# reciever.net
KiCad netlist of a schematic drawn in EAGLE
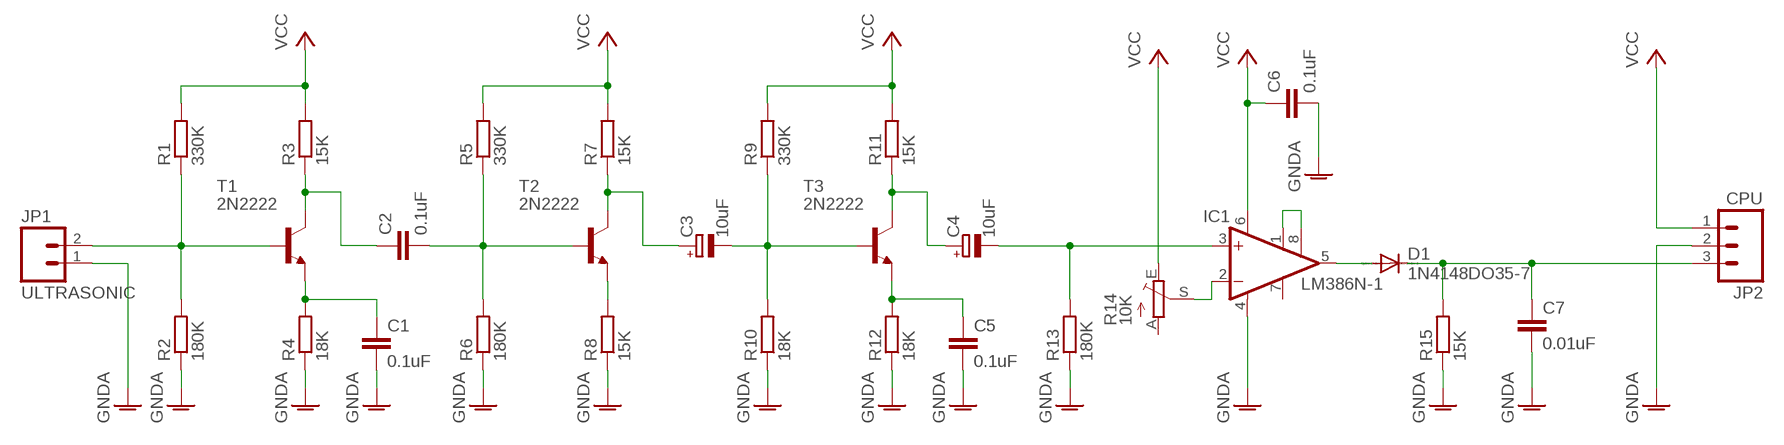
[diagram p0: schematic, sheet 1]

(export (version "E")
  (design (tool "Eeschema 10.0.6"))
  (components
    (comp (ref "C1")
      (value "0.1uF")
      (footprint "eagle-import:C050-025X075")
      (libsource (lib "eagle-import") (part "C-EU050-025X075"))
    )
    (comp (ref "C2")
      (value "0.1uF")
      (footprint "eagle-import:C050-025X075")
      (libsource (lib "eagle-import") (part "C-EU050-025X075"))
    )
    (comp (ref "C3")
      (value "10uF")
      (footprint "eagle-import:E2,5-5")
      (libsource (lib "eagle-import") (part "CPOL-EUE2.5-5"))
    )
    (comp (ref "C4")
      (value "10uF")
      (footprint "eagle-import:E2,5-5")
      (libsource (lib "eagle-import") (part "CPOL-EUE2.5-5"))
    )
    (comp (ref "C5")
      (value "0.1uF")
      (footprint "eagle-import:C050-025X075")
      (libsource (lib "eagle-import") (part "C-EU050-025X075"))
    )
    (comp (ref "C6")
      (value "0.1uF")
      (footprint "eagle-import:C050-025X075")
      (libsource (lib "eagle-import") (part "C-EU050-025X075"))
    )
    (comp (ref "C7")
      (value "0.01uF")
      (footprint "eagle-import:C050-025X075")
      (libsource (lib "eagle-import") (part "C-EU050-025X075"))
    )
    (comp (ref "D1")
      (value "1N4148DO35-7")
      (footprint "eagle-import:DO35-7")
      (libsource (lib "eagle-import") (part "1N4148DO35-7"))
    )
    (comp (ref "IC1")
      (value "LM386N-1")
      (footprint "eagle-import:DIL08")
      (libsource (lib "eagle-import") (part "LM386?-N1"))
    )
    (comp (ref "JP1")
      (value "ULTRASONIC")
      (footprint "eagle-import:JST-2-PTH-VERT")
      (libsource (lib "eagle-import") (part "M02JST-PTH-VERT"))
    )
    (comp (ref "JP2")
      (value "CPU")
      (footprint "eagle-import:JST-3-PTH-VERT")
      (libsource (lib "eagle-import") (part "M03JST-PTH-VERT"))
    )
    (comp (ref "R1")
      (value "330K")
      (footprint "eagle-import:0204_7")
      (libsource (lib "eagle-import") (part "R-EU_0204/7"))
    )
    (comp (ref "R2")
      (value "180K")
      (footprint "eagle-import:0204_7")
      (libsource (lib "eagle-import") (part "R-EU_0204/7"))
    )
    (comp (ref "R3")
      (value "15K")
      (footprint "eagle-import:0204_7")
      (libsource (lib "eagle-import") (part "R-EU_0204/7"))
    )
    (comp (ref "R4")
      (value "18K")
      (footprint "eagle-import:0204_7")
      (libsource (lib "eagle-import") (part "R-EU_0204/7"))
    )
    (comp (ref "R5")
      (value "330K")
      (footprint "eagle-import:0204_7")
      (libsource (lib "eagle-import") (part "R-EU_0204/7"))
    )
    (comp (ref "R6")
      (value "180K")
      (footprint "eagle-import:0204_7")
      (libsource (lib "eagle-import") (part "R-EU_0204/7"))
    )
    (comp (ref "R7")
      (value "15K")
      (footprint "eagle-import:0204_7")
      (libsource (lib "eagle-import") (part "R-EU_0204/7"))
    )
    (comp (ref "R8")
      (value "15K")
      (footprint "eagle-import:0204_7")
      (libsource (lib "eagle-import") (part "R-EU_0204/7"))
    )
    (comp (ref "R9")
      (value "330K")
      (footprint "eagle-import:0204_7")
      (libsource (lib "eagle-import") (part "R-EU_0204/7"))
    )
    (comp (ref "R10")
      (value "18K")
      (footprint "eagle-import:0204_7")
      (libsource (lib "eagle-import") (part "R-EU_0204/7"))
    )
    (comp (ref "R11")
      (value "15K")
      (footprint "eagle-import:0204_7")
      (libsource (lib "eagle-import") (part "R-EU_0204/7"))
    )
    (comp (ref "R12")
      (value "18K")
      (footprint "eagle-import:0204_7")
      (libsource (lib "eagle-import") (part "R-EU_0204/7"))
    )
    (comp (ref "R13")
      (value "180K")
      (footprint "eagle-import:0204_7")
      (libsource (lib "eagle-import") (part "R-EU_0204/7"))
    )
    (comp (ref "R14")
      (value "10K")
      (footprint "eagle-import:B25P")
      (libsource (lib "eagle-import") (part "TRIM_EU-B25P"))
    )
    (comp (ref "R15")
      (value "15K")
      (footprint "eagle-import:0204_7")
      (libsource (lib "eagle-import") (part "R-EU_0204/7"))
    )
    (comp (ref "T1")
      (value "2N2222")
      (footprint "eagle-import:TO92-EBC")
      (libsource (lib "eagle-import") (part "-NPN-TO92-EBC"))
    )
    (comp (ref "T2")
      (value "2N2222")
      (footprint "eagle-import:TO92-EBC")
      (libsource (lib "eagle-import") (part "-NPN-TO92-EBC"))
    )
    (comp (ref "T3")
      (value "2N2222")
      (footprint "eagle-import:TO92-EBC")
      (libsource (lib "eagle-import") (part "-NPN-TO92-EBC"))
    )
  )
  (nets
    (net (code "1") (name "GNDA") (class "Default")
      (node (ref "C1") (pin "2") (pinfunction "2_2") (pintype "passive"))
      (node (ref "C5") (pin "2") (pinfunction "2_2") (pintype "passive"))
      (node (ref "C6") (pin "2") (pinfunction "2_2") (pintype "passive"))
      (node (ref "C7") (pin "2") (pinfunction "2_2") (pintype "passive"))
      (node (ref "IC1") (pin "4") (pinfunction "GND_4") (pintype "power_in"))
      (node (ref "JP1") (pin "1") (pinfunction "1_1") (pintype "passive"))
      (node (ref "JP2") (pin "2") (pinfunction "2_2") (pintype "passive"))
      (node (ref "R10") (pin "1") (pinfunction "1_1") (pintype "passive"))
      (node (ref "R12") (pin "1") (pinfunction "1_1") (pintype "passive"))
      (node (ref "R13") (pin "1") (pinfunction "1_1") (pintype "passive"))
      (node (ref "R15") (pin "1") (pinfunction "1_1") (pintype "passive"))
      (node (ref "R2") (pin "1") (pinfunction "1_1") (pintype "passive"))
      (node (ref "R4") (pin "1") (pinfunction "1_1") (pintype "passive"))
      (node (ref "R6") (pin "1") (pinfunction "1_1") (pintype "passive"))
      (node (ref "R8") (pin "1") (pinfunction "1_1") (pintype "passive"))
    )
    (net (code "2") (name "Net-(C1-Pad1)") (class "Default")
      (node (ref "C1") (pin "1") (pinfunction "1_1") (pintype "passive"))
      (node (ref "R4") (pin "2") (pinfunction "2_2") (pintype "passive"))
      (node (ref "T1") (pin "E") (pinfunction "E_E") (pintype "passive"))
    )
    (net (code "3") (name "Net-(C2-Pad1)") (class "Default")
      (node (ref "C2") (pin "1") (pinfunction "1_1") (pintype "passive"))
      (node (ref "R3") (pin "1") (pinfunction "1_1") (pintype "passive"))
      (node (ref "T1") (pin "C") (pinfunction "C_C") (pintype "passive"))
    )
    (net (code "4") (name "Net-(C2-Pad2)") (class "Default")
      (node (ref "C2") (pin "2") (pinfunction "2_2") (pintype "passive"))
      (node (ref "R5") (pin "1") (pinfunction "1_1") (pintype "passive"))
      (node (ref "R6") (pin "2") (pinfunction "2_2") (pintype "passive"))
      (node (ref "T2") (pin "B") (pinfunction "B_B") (pintype "passive"))
    )
    (net (code "5") (name "Net-(C3-Pad+)") (class "Default")
      (node (ref "C3") (pin "+") (pinfunction "+_+") (pintype "passive"))
      (node (ref "R7") (pin "1") (pinfunction "1_1") (pintype "passive"))
      (node (ref "T2") (pin "C") (pinfunction "C_C") (pintype "passive"))
    )
    (net (code "6") (name "Net-(C3-Pad-)") (class "Default")
      (node (ref "C3") (pin "-") (pinfunction "-_-") (pintype "passive"))
      (node (ref "R10") (pin "2") (pinfunction "2_2") (pintype "passive"))
      (node (ref "R9") (pin "1") (pinfunction "1_1") (pintype "passive"))
      (node (ref "T3") (pin "B") (pinfunction "B_B") (pintype "passive"))
    )
    (net (code "7") (name "Net-(C4-Pad+)") (class "Default")
      (node (ref "C4") (pin "+") (pinfunction "+_+") (pintype "passive"))
      (node (ref "R11") (pin "1") (pinfunction "1_1") (pintype "passive"))
      (node (ref "T3") (pin "C") (pinfunction "C_C") (pintype "passive"))
    )
    (net (code "8") (name "Net-(C5-Pad1)") (class "Default")
      (node (ref "C5") (pin "1") (pinfunction "1_1") (pintype "passive"))
      (node (ref "R12") (pin "2") (pinfunction "2_2") (pintype "passive"))
      (node (ref "T3") (pin "E") (pinfunction "E_E") (pintype "passive"))
    )
    (net (code "9") (name "Net-(C7-Pad1)") (class "Default")
      (node (ref "C7") (pin "1") (pinfunction "1_1") (pintype "passive"))
      (node (ref "D1") (pin "C") (pinfunction "C_C") (pintype "passive"))
      (node (ref "JP2") (pin "3") (pinfunction "3_3") (pintype "passive"))
      (node (ref "R15") (pin "2") (pinfunction "2_2") (pintype "passive"))
    )
    (net (code "10") (name "Net-(IC1-+IN)") (class "Default")
      (node (ref "C4") (pin "-") (pinfunction "-_-") (pintype "passive"))
      (node (ref "IC1") (pin "3") (pinfunction "+IN_3") (pintype "input"))
      (node (ref "R13") (pin "2") (pinfunction "2_2") (pintype "passive"))
    )
    (net (code "11") (name "Net-(IC1--IN)") (class "Default")
      (node (ref "IC1") (pin "2") (pinfunction "-IN_2") (pintype "input"))
      (node (ref "R14") (pin "S") (pinfunction "S_S") (pintype "passive"))
    )
    (net (code "12") (name "Net-(IC1-GAIN-Pad1)") (class "Default")
      (node (ref "IC1") (pin "1") (pinfunction "GAIN_1") (pintype "passive"))
      (node (ref "IC1") (pin "8") (pinfunction "GAIN_8") (pintype "passive"))
    )
    (net (code "13") (name "Net-(IC1-OUT)") (class "Default")
      (node (ref "D1") (pin "A") (pinfunction "A_A") (pintype "passive"))
      (node (ref "IC1") (pin "5") (pinfunction "OUT_5") (pintype "output"))
    )
    (net (code "14") (name "Net-(JP1-Pad2)") (class "Default")
      (node (ref "JP1") (pin "2") (pinfunction "2_2") (pintype "passive"))
      (node (ref "R1") (pin "1") (pinfunction "1_1") (pintype "passive"))
      (node (ref "R2") (pin "2") (pinfunction "2_2") (pintype "passive"))
      (node (ref "T1") (pin "B") (pinfunction "B_B") (pintype "passive"))
    )
    (net (code "15") (name "Net-(R8-Pad2)") (class "Default")
      (node (ref "R8") (pin "2") (pinfunction "2_2") (pintype "passive"))
      (node (ref "T2") (pin "E") (pinfunction "E_E") (pintype "passive"))
    )
    (net (code "16") (name "VCC") (class "Default")
      (node (ref "C6") (pin "1") (pinfunction "1_1") (pintype "passive"))
      (node (ref "IC1") (pin "6") (pinfunction "VS_6") (pintype "power_in"))
      (node (ref "JP2") (pin "1") (pinfunction "1_1") (pintype "passive"))
      (node (ref "R1") (pin "2") (pinfunction "2_2") (pintype "passive"))
      (node (ref "R11") (pin "2") (pinfunction "2_2") (pintype "passive"))
      (node (ref "R14") (pin "E") (pinfunction "E_E") (pintype "passive"))
      (node (ref "R3") (pin "2") (pinfunction "2_2") (pintype "passive"))
      (node (ref "R5") (pin "2") (pinfunction "2_2") (pintype "passive"))
      (node (ref "R7") (pin "2") (pinfunction "2_2") (pintype "passive"))
      (node (ref "R9") (pin "2") (pinfunction "2_2") (pintype "passive"))
    )
    (net (code "17") (name "unconnected-(IC1-BYPASS-Pad7)") (class "Default")
      (node (ref "IC1") (pin "7") (pinfunction "BYPASS_7") (pintype "passive"))
    )
    (net (code "18") (name "unconnected-(R14-PadA)") (class "Default")
      (node (ref "R14") (pin "A") (pinfunction "A_A") (pintype "passive"))
    )
  )
)
